# pico-hd6303.net
KiCad netlist of a schematic drawn in EAGLE
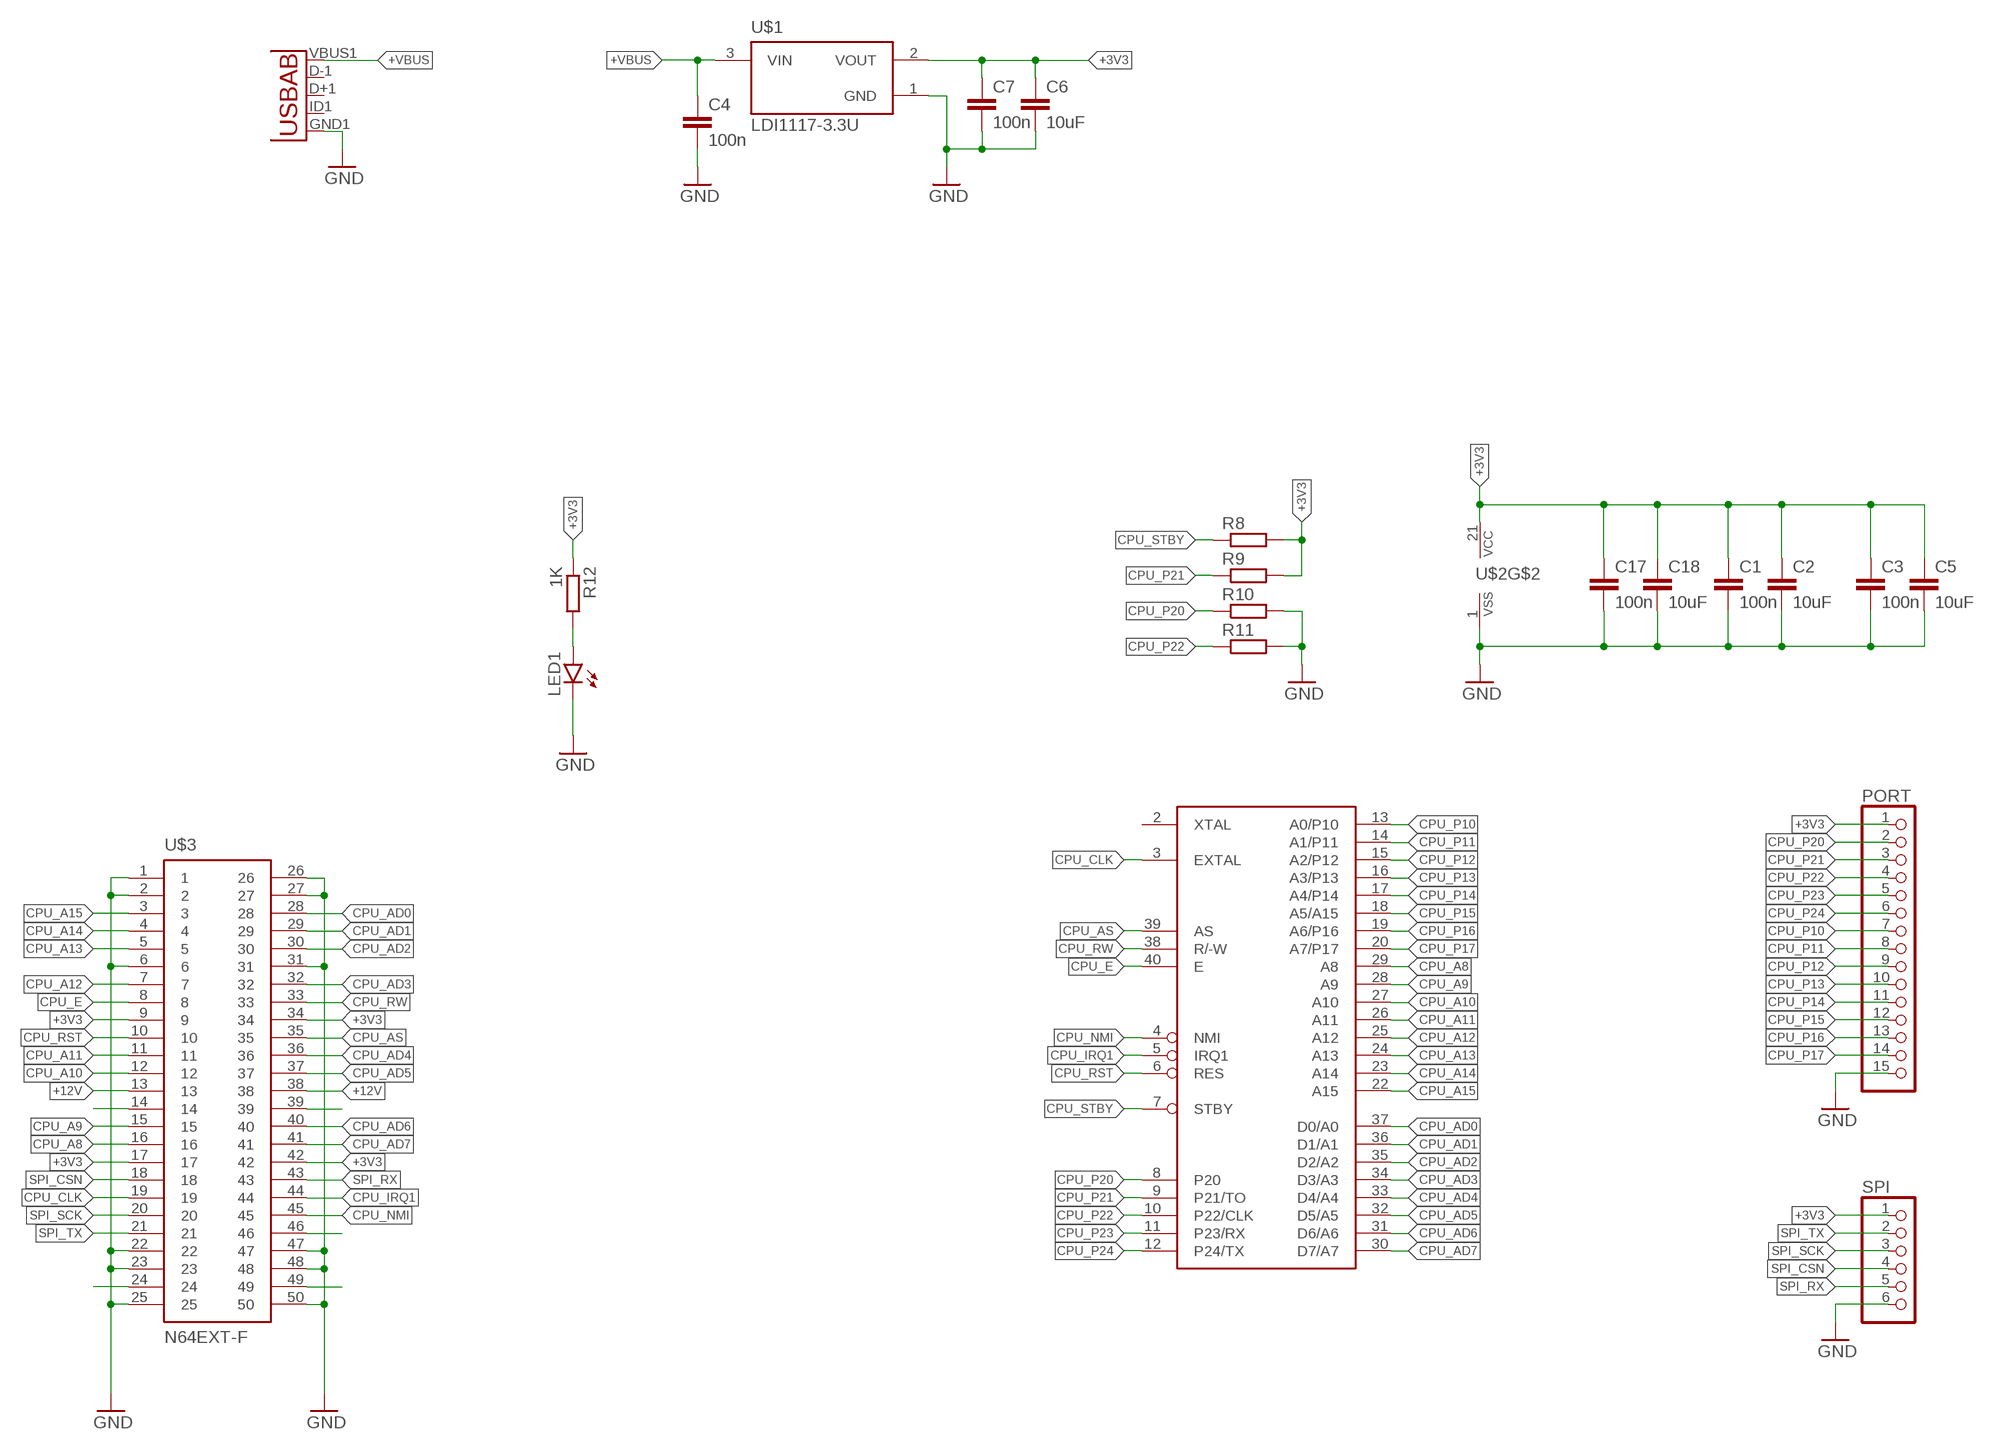
[diagram p0: schematic, sheet 1]

(export (version "E")
  (design (tool "Eeschema 10.0.6"))
  (components
    (comp (ref "C1")
      (value "100n")
      (footprint "eagle-import:C0603")
      (libsource (lib "eagle-import") (part "C-EUC0603"))
    )
    (comp (ref "C2")
      (value "10uF")
      (footprint "eagle-import:C0805")
      (libsource (lib "eagle-import") (part "resistor_348_C-EUC0805"))
    )
    (comp (ref "C3")
      (value "100n")
      (footprint "eagle-import:C0603")
      (libsource (lib "eagle-import") (part "C-EUC0603"))
    )
    (comp (ref "C4")
      (value "100n")
      (footprint "eagle-import:C0402")
      (libsource (lib "eagle-import") (part "rcl_334_C-EUC0402"))
    )
    (comp (ref "C5")
      (value "10uF")
      (footprint "eagle-import:C0805")
      (libsource (lib "eagle-import") (part "resistor_348_C-EUC0805"))
    )
    (comp (ref "C6")
      (value "10uF")
      (footprint "eagle-import:C0805")
      (libsource (lib "eagle-import") (part "resistor_348_C-EUC0805"))
    )
    (comp (ref "C7")
      (value "100n")
      (footprint "eagle-import:C0402")
      (libsource (lib "eagle-import") (part "rcl_334_C-EUC0402"))
    )
    (comp (ref "C17")
      (value "100n")
      (footprint "eagle-import:C0603")
      (libsource (lib "eagle-import") (part "C-EUC0603"))
    )
    (comp (ref "C18")
      (value "10uF")
      (footprint "eagle-import:C0805")
      (libsource (lib "eagle-import") (part "resistor_348_C-EUC0805"))
    )
    (comp (ref "LED1")
      (value "LED5MM")
      (footprint "eagle-import:LED5MM")
      (libsource (lib "eagle-import") (part "LED5MM"))
    )
    (comp (ref "PORT")
      (value "PINHD-1X15")
      (footprint "eagle-import:1X15")
      (libsource (lib "eagle-import") (part "PINHD-1X15"))
    )
    (comp (ref "R8")
      (value "R-EU_R0603")
      (footprint "eagle-import:R0603")
      (libsource (lib "eagle-import") (part "R-EU_R0603"))
    )
    (comp (ref "R9")
      (value "R-EU_R0603")
      (footprint "eagle-import:R0603")
      (libsource (lib "eagle-import") (part "R-EU_R0603"))
    )
    (comp (ref "R10")
      (value "R-EU_R0603")
      (footprint "eagle-import:R0603")
      (libsource (lib "eagle-import") (part "R-EU_R0603"))
    )
    (comp (ref "R11")
      (value "R-EU_R0603")
      (footprint "eagle-import:R0603")
      (libsource (lib "eagle-import") (part "R-EU_R0603"))
    )
    (comp (ref "R12")
      (value "1K")
      (footprint "eagle-import:R0603")
      (libsource (lib "eagle-import") (part "R-EU_R0603"))
    )
    (comp (ref "SPI")
      (value "PINHD-1X6")
      (footprint "eagle-import:1X06")
      (libsource (lib "eagle-import") (part "PINHD-1X6"))
    )
    (comp (ref "U$1")
      (value "LDI1117-3.3U")
      (footprint "eagle-import:LDI1117-3.3U")
      (libsource (lib "eagle-import") (part "LDI1117-3.3U"))
    )
    (comp (ref "U$2")
      (value "HD63B03PRP")
      (footprint "eagle-import:DIL40")
      (libsource (lib "eagle-import") (part "HD63B03PRP"))
    )
    (comp (ref "U$3")
      (value "N64EXT-F")
      (footprint "eagle-import:N64F")
      (libsource (lib "eagle-import") (part "N64EXT-F"))
    )
    (comp (ref "U2")
      (value "USB\"\"")
      (footprint "eagle-import:USB-MICRO-SMD")
      (libsource (lib "eagle-import") (part "USB{dblquote}{dblquote}"))
    )
  )
  (nets
    (net (code "1") (name "+3V3") (class "Default")
      (node (ref "C1") (pin "1") (pinfunction "1_1") (pintype "passive"))
      (node (ref "C17") (pin "1") (pinfunction "1_1") (pintype "passive"))
      (node (ref "C18") (pin "1") (pinfunction "1_1") (pintype "passive"))
      (node (ref "C2") (pin "1") (pinfunction "1_1") (pintype "passive"))
      (node (ref "C3") (pin "1") (pinfunction "1_1") (pintype "passive"))
      (node (ref "C5") (pin "1") (pinfunction "1_1") (pintype "passive"))
      (node (ref "C6") (pin "1") (pinfunction "1_1") (pintype "passive"))
      (node (ref "C7") (pin "1") (pinfunction "1_1") (pintype "passive"))
      (node (ref "PORT") (pin "1") (pinfunction "1_1") (pintype "passive"))
      (node (ref "R12") (pin "1") (pinfunction "1_1") (pintype "passive"))
      (node (ref "R8") (pin "2") (pinfunction "2_2") (pintype "passive"))
      (node (ref "R9") (pin "2") (pinfunction "2_2") (pintype "passive"))
      (node (ref "SPI") (pin "1") (pinfunction "1_1") (pintype "passive"))
      (node (ref "U$1") (pin "2") (pinfunction "VOUT_2") (pintype "output"))
      (node (ref "U$2") (pin "21") (pinfunction "VCC_21") (pintype "power_in"))
      (node (ref "U$3") (pin "17") (pinfunction "17_17") (pintype "passive"))
      (node (ref "U$3") (pin "34") (pinfunction "34_34") (pintype "passive"))
      (node (ref "U$3") (pin "42") (pinfunction "42_42") (pintype "passive"))
      (node (ref "U$3") (pin "9") (pinfunction "9_9") (pintype "passive"))
    )
    (net (code "2") (name "+12V") (class "Default")
      (node (ref "U$3") (pin "13") (pinfunction "13_13") (pintype "passive"))
      (node (ref "U$3") (pin "38") (pinfunction "38_38") (pintype "passive"))
    )
    (net (code "3") (name "+VBUS") (class "Default")
      (node (ref "C4") (pin "1") (pinfunction "1_1") (pintype "passive"))
      (node (ref "U$1") (pin "3") (pinfunction "VIN_3") (pintype "input"))
      (node (ref "U2") (pin "VBUS1") (pinfunction "VBUS_VBUS1") (pintype "bidirectional"))
    )
    (net (code "4") (name "CPU_A8") (class "Default")
      (node (ref "U$2") (pin "29") (pinfunction "A8_29") (pintype "bidirectional"))
      (node (ref "U$3") (pin "16") (pinfunction "16_16") (pintype "passive"))
    )
    (net (code "5") (name "CPU_A9") (class "Default")
      (node (ref "U$2") (pin "28") (pinfunction "A9_28") (pintype "bidirectional"))
      (node (ref "U$3") (pin "15") (pinfunction "15_15") (pintype "passive"))
    )
    (net (code "6") (name "CPU_A10") (class "Default")
      (node (ref "U$2") (pin "27") (pinfunction "A10_27") (pintype "bidirectional"))
      (node (ref "U$3") (pin "12") (pinfunction "12_12") (pintype "passive"))
    )
    (net (code "7") (name "CPU_A11") (class "Default")
      (node (ref "U$2") (pin "26") (pinfunction "A11_26") (pintype "bidirectional"))
      (node (ref "U$3") (pin "11") (pinfunction "11_11") (pintype "passive"))
    )
    (net (code "8") (name "CPU_A12") (class "Default")
      (node (ref "U$2") (pin "25") (pinfunction "A12_25") (pintype "bidirectional"))
      (node (ref "U$3") (pin "7") (pinfunction "7_7") (pintype "passive"))
    )
    (net (code "9") (name "CPU_A13") (class "Default")
      (node (ref "U$2") (pin "24") (pinfunction "A13_24") (pintype "bidirectional"))
      (node (ref "U$3") (pin "5") (pinfunction "5_5") (pintype "passive"))
    )
    (net (code "10") (name "CPU_A14") (class "Default")
      (node (ref "U$2") (pin "23") (pinfunction "A14_23") (pintype "bidirectional"))
      (node (ref "U$3") (pin "4") (pinfunction "4_4") (pintype "passive"))
    )
    (net (code "11") (name "CPU_A15") (class "Default")
      (node (ref "U$2") (pin "22") (pinfunction "A15_22") (pintype "bidirectional"))
      (node (ref "U$3") (pin "3") (pinfunction "3_3") (pintype "passive"))
    )
    (net (code "12") (name "CPU_AD0") (class "Default")
      (node (ref "U$2") (pin "37") (pinfunction "D0/A0_37") (pintype "bidirectional"))
      (node (ref "U$3") (pin "28") (pinfunction "28_28") (pintype "passive"))
    )
    (net (code "13") (name "CPU_AD1") (class "Default")
      (node (ref "U$2") (pin "36") (pinfunction "D1/A1_36") (pintype "bidirectional"))
      (node (ref "U$3") (pin "29") (pinfunction "29_29") (pintype "passive"))
    )
    (net (code "14") (name "CPU_AD2") (class "Default")
      (node (ref "U$2") (pin "35") (pinfunction "D2/A2_35") (pintype "bidirectional"))
      (node (ref "U$3") (pin "30") (pinfunction "30_30") (pintype "passive"))
    )
    (net (code "15") (name "CPU_AD3") (class "Default")
      (node (ref "U$2") (pin "34") (pinfunction "D3/A3_34") (pintype "bidirectional"))
      (node (ref "U$3") (pin "32") (pinfunction "32_32") (pintype "passive"))
    )
    (net (code "16") (name "CPU_AD4") (class "Default")
      (node (ref "U$2") (pin "33") (pinfunction "D4/A4_33") (pintype "bidirectional"))
      (node (ref "U$3") (pin "36") (pinfunction "36_36") (pintype "passive"))
    )
    (net (code "17") (name "CPU_AD5") (class "Default")
      (node (ref "U$2") (pin "32") (pinfunction "D5/A5_32") (pintype "bidirectional"))
      (node (ref "U$3") (pin "37") (pinfunction "37_37") (pintype "passive"))
    )
    (net (code "18") (name "CPU_AD6") (class "Default")
      (node (ref "U$2") (pin "31") (pinfunction "D6/A6_31") (pintype "bidirectional"))
      (node (ref "U$3") (pin "40") (pinfunction "40_40") (pintype "passive"))
    )
    (net (code "19") (name "CPU_AD7") (class "Default")
      (node (ref "U$2") (pin "30") (pinfunction "D7/A7_30") (pintype "bidirectional"))
      (node (ref "U$3") (pin "41") (pinfunction "41_41") (pintype "passive"))
    )
    (net (code "20") (name "CPU_AS") (class "Default")
      (node (ref "U$2") (pin "39") (pinfunction "AS_39") (pintype "output"))
      (node (ref "U$3") (pin "35") (pinfunction "35_35") (pintype "passive"))
    )
    (net (code "21") (name "CPU_CLK") (class "Default")
      (node (ref "U$2") (pin "3") (pinfunction "EXTAL_3") (pintype "output"))
      (node (ref "U$3") (pin "19") (pinfunction "19_19") (pintype "passive"))
    )
    (net (code "22") (name "CPU_E") (class "Default")
      (node (ref "U$2") (pin "40") (pinfunction "E_40") (pintype "output"))
      (node (ref "U$3") (pin "8") (pinfunction "8_8") (pintype "passive"))
    )
    (net (code "23") (name "CPU_IRQ1") (class "Default")
      (node (ref "U$2") (pin "5") (pinfunction "IRQ1_5") (pintype "input"))
      (node (ref "U$3") (pin "44") (pinfunction "44_44") (pintype "passive"))
    )
    (net (code "24") (name "CPU_NMI") (class "Default")
      (node (ref "U$2") (pin "4") (pinfunction "NMI_4") (pintype "input"))
      (node (ref "U$3") (pin "45") (pinfunction "45_45") (pintype "passive"))
    )
    (net (code "25") (name "CPU_P10") (class "Default")
      (node (ref "PORT") (pin "7") (pinfunction "7_7") (pintype "passive"))
      (node (ref "U$2") (pin "13") (pinfunction "A0/P10_13") (pintype "bidirectional"))
    )
    (net (code "26") (name "CPU_P11") (class "Default")
      (node (ref "PORT") (pin "8") (pinfunction "8_8") (pintype "passive"))
      (node (ref "U$2") (pin "14") (pinfunction "A1/P11_14") (pintype "bidirectional"))
    )
    (net (code "27") (name "CPU_P12") (class "Default")
      (node (ref "PORT") (pin "9") (pinfunction "9_9") (pintype "passive"))
      (node (ref "U$2") (pin "15") (pinfunction "A2/P12_15") (pintype "bidirectional"))
    )
    (net (code "28") (name "CPU_P13") (class "Default")
      (node (ref "PORT") (pin "10") (pinfunction "10_10") (pintype "passive"))
      (node (ref "U$2") (pin "16") (pinfunction "A3/P13_16") (pintype "bidirectional"))
    )
    (net (code "29") (name "CPU_P14") (class "Default")
      (node (ref "PORT") (pin "11") (pinfunction "11_11") (pintype "passive"))
      (node (ref "U$2") (pin "17") (pinfunction "A4/P14_17") (pintype "bidirectional"))
    )
    (net (code "30") (name "CPU_P15") (class "Default")
      (node (ref "PORT") (pin "12") (pinfunction "12_12") (pintype "passive"))
      (node (ref "U$2") (pin "18") (pinfunction "A5/A15_18") (pintype "bidirectional"))
    )
    (net (code "31") (name "CPU_P16") (class "Default")
      (node (ref "PORT") (pin "13") (pinfunction "13_13") (pintype "passive"))
      (node (ref "U$2") (pin "19") (pinfunction "A6/P16_19") (pintype "bidirectional"))
    )
    (net (code "32") (name "CPU_P17") (class "Default")
      (node (ref "PORT") (pin "14") (pinfunction "14_14") (pintype "passive"))
      (node (ref "U$2") (pin "20") (pinfunction "A7/P17_20") (pintype "bidirectional"))
    )
    (net (code "33") (name "CPU_P20") (class "Default")
      (node (ref "PORT") (pin "2") (pinfunction "2_2") (pintype "passive"))
      (node (ref "R10") (pin "1") (pinfunction "1_1") (pintype "passive"))
      (node (ref "U$2") (pin "8") (pinfunction "P20_8") (pintype "bidirectional"))
    )
    (net (code "34") (name "CPU_P21") (class "Default")
      (node (ref "PORT") (pin "3") (pinfunction "3_3") (pintype "passive"))
      (node (ref "R9") (pin "1") (pinfunction "1_1") (pintype "passive"))
      (node (ref "U$2") (pin "9") (pinfunction "P21/TO_9") (pintype "bidirectional"))
    )
    (net (code "35") (name "CPU_P22") (class "Default")
      (node (ref "PORT") (pin "4") (pinfunction "4_4") (pintype "passive"))
      (node (ref "R11") (pin "1") (pinfunction "1_1") (pintype "passive"))
      (node (ref "U$2") (pin "10") (pinfunction "P22/CLK_10") (pintype "bidirectional"))
    )
    (net (code "36") (name "CPU_P23") (class "Default")
      (node (ref "PORT") (pin "5") (pinfunction "5_5") (pintype "passive"))
      (node (ref "U$2") (pin "11") (pinfunction "P23/RX_11") (pintype "bidirectional"))
    )
    (net (code "37") (name "CPU_P24") (class "Default")
      (node (ref "PORT") (pin "6") (pinfunction "6_6") (pintype "passive"))
      (node (ref "U$2") (pin "12") (pinfunction "P24/TX_12") (pintype "bidirectional"))
    )
    (net (code "38") (name "CPU_RST") (class "Default")
      (node (ref "U$2") (pin "6") (pinfunction "RES_6") (pintype "input"))
      (node (ref "U$3") (pin "10") (pinfunction "10_10") (pintype "passive"))
    )
    (net (code "39") (name "CPU_RW") (class "Default")
      (node (ref "U$2") (pin "38") (pinfunction "R/-W_38") (pintype "output"))
      (node (ref "U$3") (pin "33") (pinfunction "33_33") (pintype "passive"))
    )
    (net (code "40") (name "CPU_STBY") (class "Default")
      (node (ref "R8") (pin "1") (pinfunction "1_1") (pintype "passive"))
      (node (ref "U$2") (pin "7") (pinfunction "STBY_7") (pintype "output"))
    )
    (net (code "41") (name "GND") (class "Default")
      (node (ref "C1") (pin "2") (pinfunction "2_2") (pintype "passive"))
      (node (ref "C17") (pin "2") (pinfunction "2_2") (pintype "passive"))
      (node (ref "C18") (pin "2") (pinfunction "2_2") (pintype "passive"))
      (node (ref "C2") (pin "2") (pinfunction "2_2") (pintype "passive"))
      (node (ref "C3") (pin "2") (pinfunction "2_2") (pintype "passive"))
      (node (ref "C4") (pin "2") (pinfunction "2_2") (pintype "passive"))
      (node (ref "C5") (pin "2") (pinfunction "2_2") (pintype "passive"))
      (node (ref "C6") (pin "2") (pinfunction "2_2") (pintype "passive"))
      (node (ref "C7") (pin "2") (pinfunction "2_2") (pintype "passive"))
      (node (ref "LED1") (pin "K") (pinfunction "C_K") (pintype "passive"))
      (node (ref "PORT") (pin "15") (pinfunction "15_15") (pintype "passive"))
      (node (ref "R10") (pin "2") (pinfunction "2_2") (pintype "passive"))
      (node (ref "R11") (pin "2") (pinfunction "2_2") (pintype "passive"))
      (node (ref "SPI") (pin "6") (pinfunction "6_6") (pintype "passive"))
      (node (ref "U$1") (pin "1") (pinfunction "GND_1") (pintype "power_in"))
      (node (ref "U$2") (pin "1") (pinfunction "VSS_1") (pintype "power_in"))
      (node (ref "U$3") (pin "1") (pinfunction "1_1") (pintype "passive"))
      (node (ref "U$3") (pin "2") (pinfunction "2_2") (pintype "passive"))
      (node (ref "U$3") (pin "22") (pinfunction "22_22") (pintype "passive"))
      (node (ref "U$3") (pin "23") (pinfunction "23_23") (pintype "passive"))
      (node (ref "U$3") (pin "25") (pinfunction "25_25") (pintype "passive"))
      (node (ref "U$3") (pin "26") (pinfunction "26_26") (pintype "passive"))
      (node (ref "U$3") (pin "27") (pinfunction "27_27") (pintype "passive"))
      (node (ref "U$3") (pin "31") (pinfunction "31_31") (pintype "passive"))
      (node (ref "U$3") (pin "47") (pinfunction "47_47") (pintype "passive"))
      (node (ref "U$3") (pin "48") (pinfunction "48_48") (pintype "passive"))
      (node (ref "U$3") (pin "50") (pinfunction "50_50") (pintype "passive"))
      (node (ref "U$3") (pin "6") (pinfunction "6_6") (pintype "passive"))
      (node (ref "U2") (pin "GND1") (pinfunction "GND_GND1") (pintype "bidirectional"))
    )
    (net (code "42") (name "Net-(LED1-PadA)") (class "Default")
      (node (ref "LED1") (pin "A") (pinfunction "A_A") (pintype "passive"))
      (node (ref "R12") (pin "2") (pinfunction "2_2") (pintype "passive"))
    )
    (net (code "43") (name "SPI_CSN") (class "Default")
      (node (ref "SPI") (pin "4") (pinfunction "4_4") (pintype "passive"))
      (node (ref "U$3") (pin "18") (pinfunction "18_18") (pintype "passive"))
    )
    (net (code "44") (name "SPI_RX") (class "Default")
      (node (ref "SPI") (pin "5") (pinfunction "5_5") (pintype "passive"))
      (node (ref "U$3") (pin "43") (pinfunction "43_43") (pintype "passive"))
    )
    (net (code "45") (name "SPI_SCK") (class "Default")
      (node (ref "SPI") (pin "3") (pinfunction "3_3") (pintype "passive"))
      (node (ref "U$3") (pin "20") (pinfunction "20_20") (pintype "passive"))
    )
    (net (code "46") (name "SPI_TX") (class "Default")
      (node (ref "SPI") (pin "2") (pinfunction "2_2") (pintype "passive"))
      (node (ref "U$3") (pin "21") (pinfunction "21_21") (pintype "passive"))
    )
    (net (code "47") (name "unconnected-(U$2A-XTAL-Pad2)") (class "Default")
      (node (ref "U$2") (pin "2") (pinfunction "XTAL_2") (pintype "input"))
    )
    (net (code "48") (name "unconnected-(U$3-Pad14)") (class "Default")
      (node (ref "U$3") (pin "14") (pinfunction "14_14") (pintype "passive"))
    )
    (net (code "49") (name "unconnected-(U$3-Pad24)") (class "Default")
      (node (ref "U$3") (pin "24") (pinfunction "24_24") (pintype "passive"))
    )
    (net (code "50") (name "unconnected-(U$3-Pad39)") (class "Default")
      (node (ref "U$3") (pin "39") (pinfunction "39_39") (pintype "passive"))
    )
    (net (code "51") (name "unconnected-(U$3-Pad46)") (class "Default")
      (node (ref "U$3") (pin "46") (pinfunction "46_46") (pintype "passive"))
    )
    (net (code "52") (name "unconnected-(U$3-Pad49)") (class "Default")
      (node (ref "U$3") (pin "49") (pinfunction "49_49") (pintype "passive"))
    )
    (net (code "53") (name "unconnected-(U2-D+-PadD+1)") (class "Default")
      (node (ref "U2") (pin "D+1") (pinfunction "D+_D+1") (pintype "bidirectional"))
    )
    (net (code "54") (name "unconnected-(U2-D--PadD-1)") (class "Default")
      (node (ref "U2") (pin "D-1") (pinfunction "D-_D-1") (pintype "bidirectional"))
    )
    (net (code "55") (name "unconnected-(U2-USBID-PadID1)") (class "Default")
      (node (ref "U2") (pin "ID1") (pinfunction "USBID_ID1") (pintype "bidirectional"))
    )
  )
)
